# board.net
KiCad netlist of a schematic drawn in EAGLE
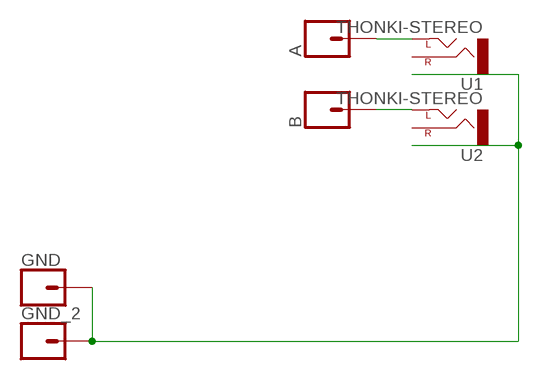
[diagram p0: schematic, sheet 1]

(export (version "E")
  (design (tool "Eeschema 10.0.6"))
  (components
    (comp (ref "A")
      (value "CONN_01")
      (footprint "eagle-import:1X01")
      (libsource (lib "eagle-import") (part "CONN_01"))
    )
    (comp (ref "B")
      (value "CONN_01")
      (footprint "eagle-import:1X01")
      (libsource (lib "eagle-import") (part "CONN_01"))
    )
    (comp (ref "GND")
      (value "CONN_01")
      (footprint "eagle-import:1X01")
      (libsource (lib "eagle-import") (part "CONN_01"))
    )
    (comp (ref "GND_2")
      (value "CONN_01")
      (footprint "eagle-import:1X01")
      (libsource (lib "eagle-import") (part "CONN_01"))
    )
    (comp (ref "U1")
      (value "THONKI-STEREO")
      (footprint "eagle-import:WQP-PJ366ST_JACK")
      (libsource (lib "eagle-import") (part "THONKI-STEREO"))
    )
    (comp (ref "U2")
      (value "THONKI-STEREO")
      (footprint "eagle-import:WQP-PJ366ST_JACK")
      (libsource (lib "eagle-import") (part "THONKI-STEREO"))
    )
  )
  (nets
    (net (code "1") (name "Net-(U1-LEFT)") (class "Default")
      (node (ref "A") (pin "1") (pinfunction "1_1") (pintype "passive"))
      (node (ref "U1") (pin "P$1_TIP") (pinfunction "LEFT_P$1_TIP") (pintype "bidirectional"))
    )
    (net (code "2") (name "Net-(U1-SLEEVE)") (class "Default")
      (node (ref "GND") (pin "1") (pinfunction "1_1") (pintype "passive"))
      (node (ref "GND_2") (pin "1") (pinfunction "1_1") (pintype "passive"))
      (node (ref "U1") (pin "P$3_SLEEVE") (pinfunction "SLEEVE_P$3_SLEEVE") (pintype "bidirectional"))
      (node (ref "U2") (pin "P$3_SLEEVE") (pinfunction "SLEEVE_P$3_SLEEVE") (pintype "bidirectional"))
    )
    (net (code "3") (name "Net-(U2-LEFT)") (class "Default")
      (node (ref "B") (pin "1") (pinfunction "1_1") (pintype "passive"))
      (node (ref "U2") (pin "P$1_TIP") (pinfunction "LEFT_P$1_TIP") (pintype "bidirectional"))
    )
    (net (code "4") (name "unconnected-(U1-RIGHT-PadP$2_SWITCH)") (class "Default")
      (node (ref "U1") (pin "P$2_SWITCH") (pinfunction "RIGHT_P$2_SWITCH") (pintype "bidirectional"))
    )
    (net (code "5") (name "unconnected-(U2-RIGHT-PadP$2_SWITCH)") (class "Default")
      (node (ref "U2") (pin "P$2_SWITCH") (pinfunction "RIGHT_P$2_SWITCH") (pintype "bidirectional"))
    )
  )
)
